# SolarConnections.net
KiCad netlist of a schematic drawn in Altium Designer
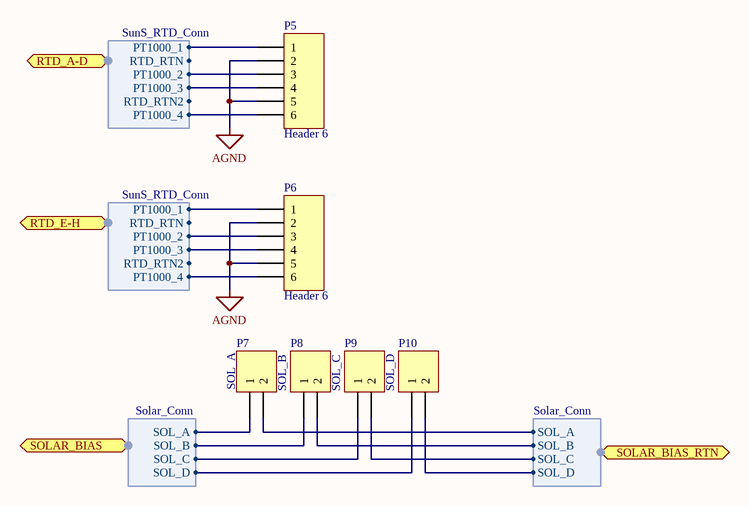
[diagram p0: SolarConnections.SchDoc]

(export (version "E")
  (design (tool "Eeschema 10.0.6"))
  (components
    (comp (ref "P5")
      (value "Header 6")
      (footprint "HDR1X6")
      (description "Header, 6-Pin")
      (fields (field (name "PUBLISHER") "Altium Limited"))
      (libsource (lib "Miscellaneous Connectors") (part "Header 6"))
    )
    (comp (ref "P6")
      (value "Header 6")
      (footprint "HDR1X6")
      (description "Header, 6-Pin")
      (fields (field (name "PUBLISHER") "Altium Limited"))
      (libsource (lib "Miscellaneous Connectors") (part "Header 6"))
    )
    (comp (ref "P7")
      (value "SOL_A")
      (footprint "HDR1X2")
      (description "Header, 2-Pin")
      (fields (field (name "PUBLISHER") "Altium Limited"))
      (libsource (lib "Miscellaneous Connectors") (part "Header 2"))
    )
    (comp (ref "P8")
      (value "SOL_B")
      (footprint "HDR1X2")
      (description "Header, 2-Pin")
      (fields (field (name "PUBLISHER") "Altium Limited"))
      (libsource (lib "Miscellaneous Connectors") (part "Header 2"))
    )
    (comp (ref "P9")
      (value "SOL_C")
      (footprint "HDR1X2")
      (description "Header, 2-Pin")
      (fields (field (name "PUBLISHER") "Altium Limited"))
      (libsource (lib "Miscellaneous Connectors") (part "Header 2"))
    )
    (comp (ref "P10")
      (value "SOL_D")
      (footprint "HDR1X2")
      (description "Header, 2-Pin")
      (fields (field (name "PUBLISHER") "Altium Limited"))
      (libsource (lib "Miscellaneous Connectors") (part "Header 2"))
    )
  )
  (nets
    (net (code "5") (name "AGND") (class "Default")
      (node (ref "P5") (pin "2") (pinfunction "2_2") (pintype "passive"))
      (node (ref "P5") (pin "5") (pinfunction "5_5") (pintype "passive"))
      (node (ref "P6") (pin "2") (pinfunction "2_2") (pintype "passive"))
      (node (ref "P6") (pin "5") (pinfunction "5_5") (pintype "passive"))
    )
    (net (code "6") (name "unconnected-(P5-Pad1)") (class "Default")
      (node (ref "P5") (pin "1") (pinfunction "1_1") (pintype "passive"))
    )
    (net (code "7") (name "unconnected-(P5-Pad3)") (class "Default")
      (node (ref "P5") (pin "3") (pinfunction "3_3") (pintype "passive"))
    )
    (net (code "8") (name "unconnected-(P5-Pad4)") (class "Default")
      (node (ref "P5") (pin "4") (pinfunction "4_4") (pintype "passive"))
    )
    (net (code "9") (name "unconnected-(P5-Pad6)") (class "Default")
      (node (ref "P5") (pin "6") (pinfunction "6_6") (pintype "passive"))
    )
    (net (code "10") (name "unconnected-(P6-Pad1)") (class "Default")
      (node (ref "P6") (pin "1") (pinfunction "1_1") (pintype "passive"))
    )
    (net (code "11") (name "unconnected-(P6-Pad3)") (class "Default")
      (node (ref "P6") (pin "3") (pinfunction "3_3") (pintype "passive"))
    )
    (net (code "12") (name "unconnected-(P6-Pad4)") (class "Default")
      (node (ref "P6") (pin "4") (pinfunction "4_4") (pintype "passive"))
    )
    (net (code "13") (name "unconnected-(P6-Pad6)") (class "Default")
      (node (ref "P6") (pin "6") (pinfunction "6_6") (pintype "passive"))
    )
    (net (code "14") (name "unconnected-(P7-Pad1)") (class "Default")
      (node (ref "P7") (pin "1") (pinfunction "1_1") (pintype "passive"))
    )
    (net (code "15") (name "unconnected-(P7-Pad2)") (class "Default")
      (node (ref "P7") (pin "2") (pinfunction "2_2") (pintype "passive"))
    )
    (net (code "16") (name "unconnected-(P8-Pad1)") (class "Default")
      (node (ref "P8") (pin "1") (pinfunction "1_1") (pintype "passive"))
    )
    (net (code "17") (name "unconnected-(P8-Pad2)") (class "Default")
      (node (ref "P8") (pin "2") (pinfunction "2_2") (pintype "passive"))
    )
    (net (code "18") (name "unconnected-(P9-Pad1)") (class "Default")
      (node (ref "P9") (pin "1") (pinfunction "1_1") (pintype "passive"))
    )
    (net (code "19") (name "unconnected-(P9-Pad2)") (class "Default")
      (node (ref "P9") (pin "2") (pinfunction "2_2") (pintype "passive"))
    )
    (net (code "20") (name "unconnected-(P10-Pad1)") (class "Default")
      (node (ref "P10") (pin "1") (pinfunction "1_1") (pintype "passive"))
    )
    (net (code "21") (name "unconnected-(P10-Pad2)") (class "Default")
      (node (ref "P10") (pin "2") (pinfunction "2_2") (pintype "passive"))
    )
  )
)
